# MCU.net
KiCad netlist of a schematic drawn in Altium Designer
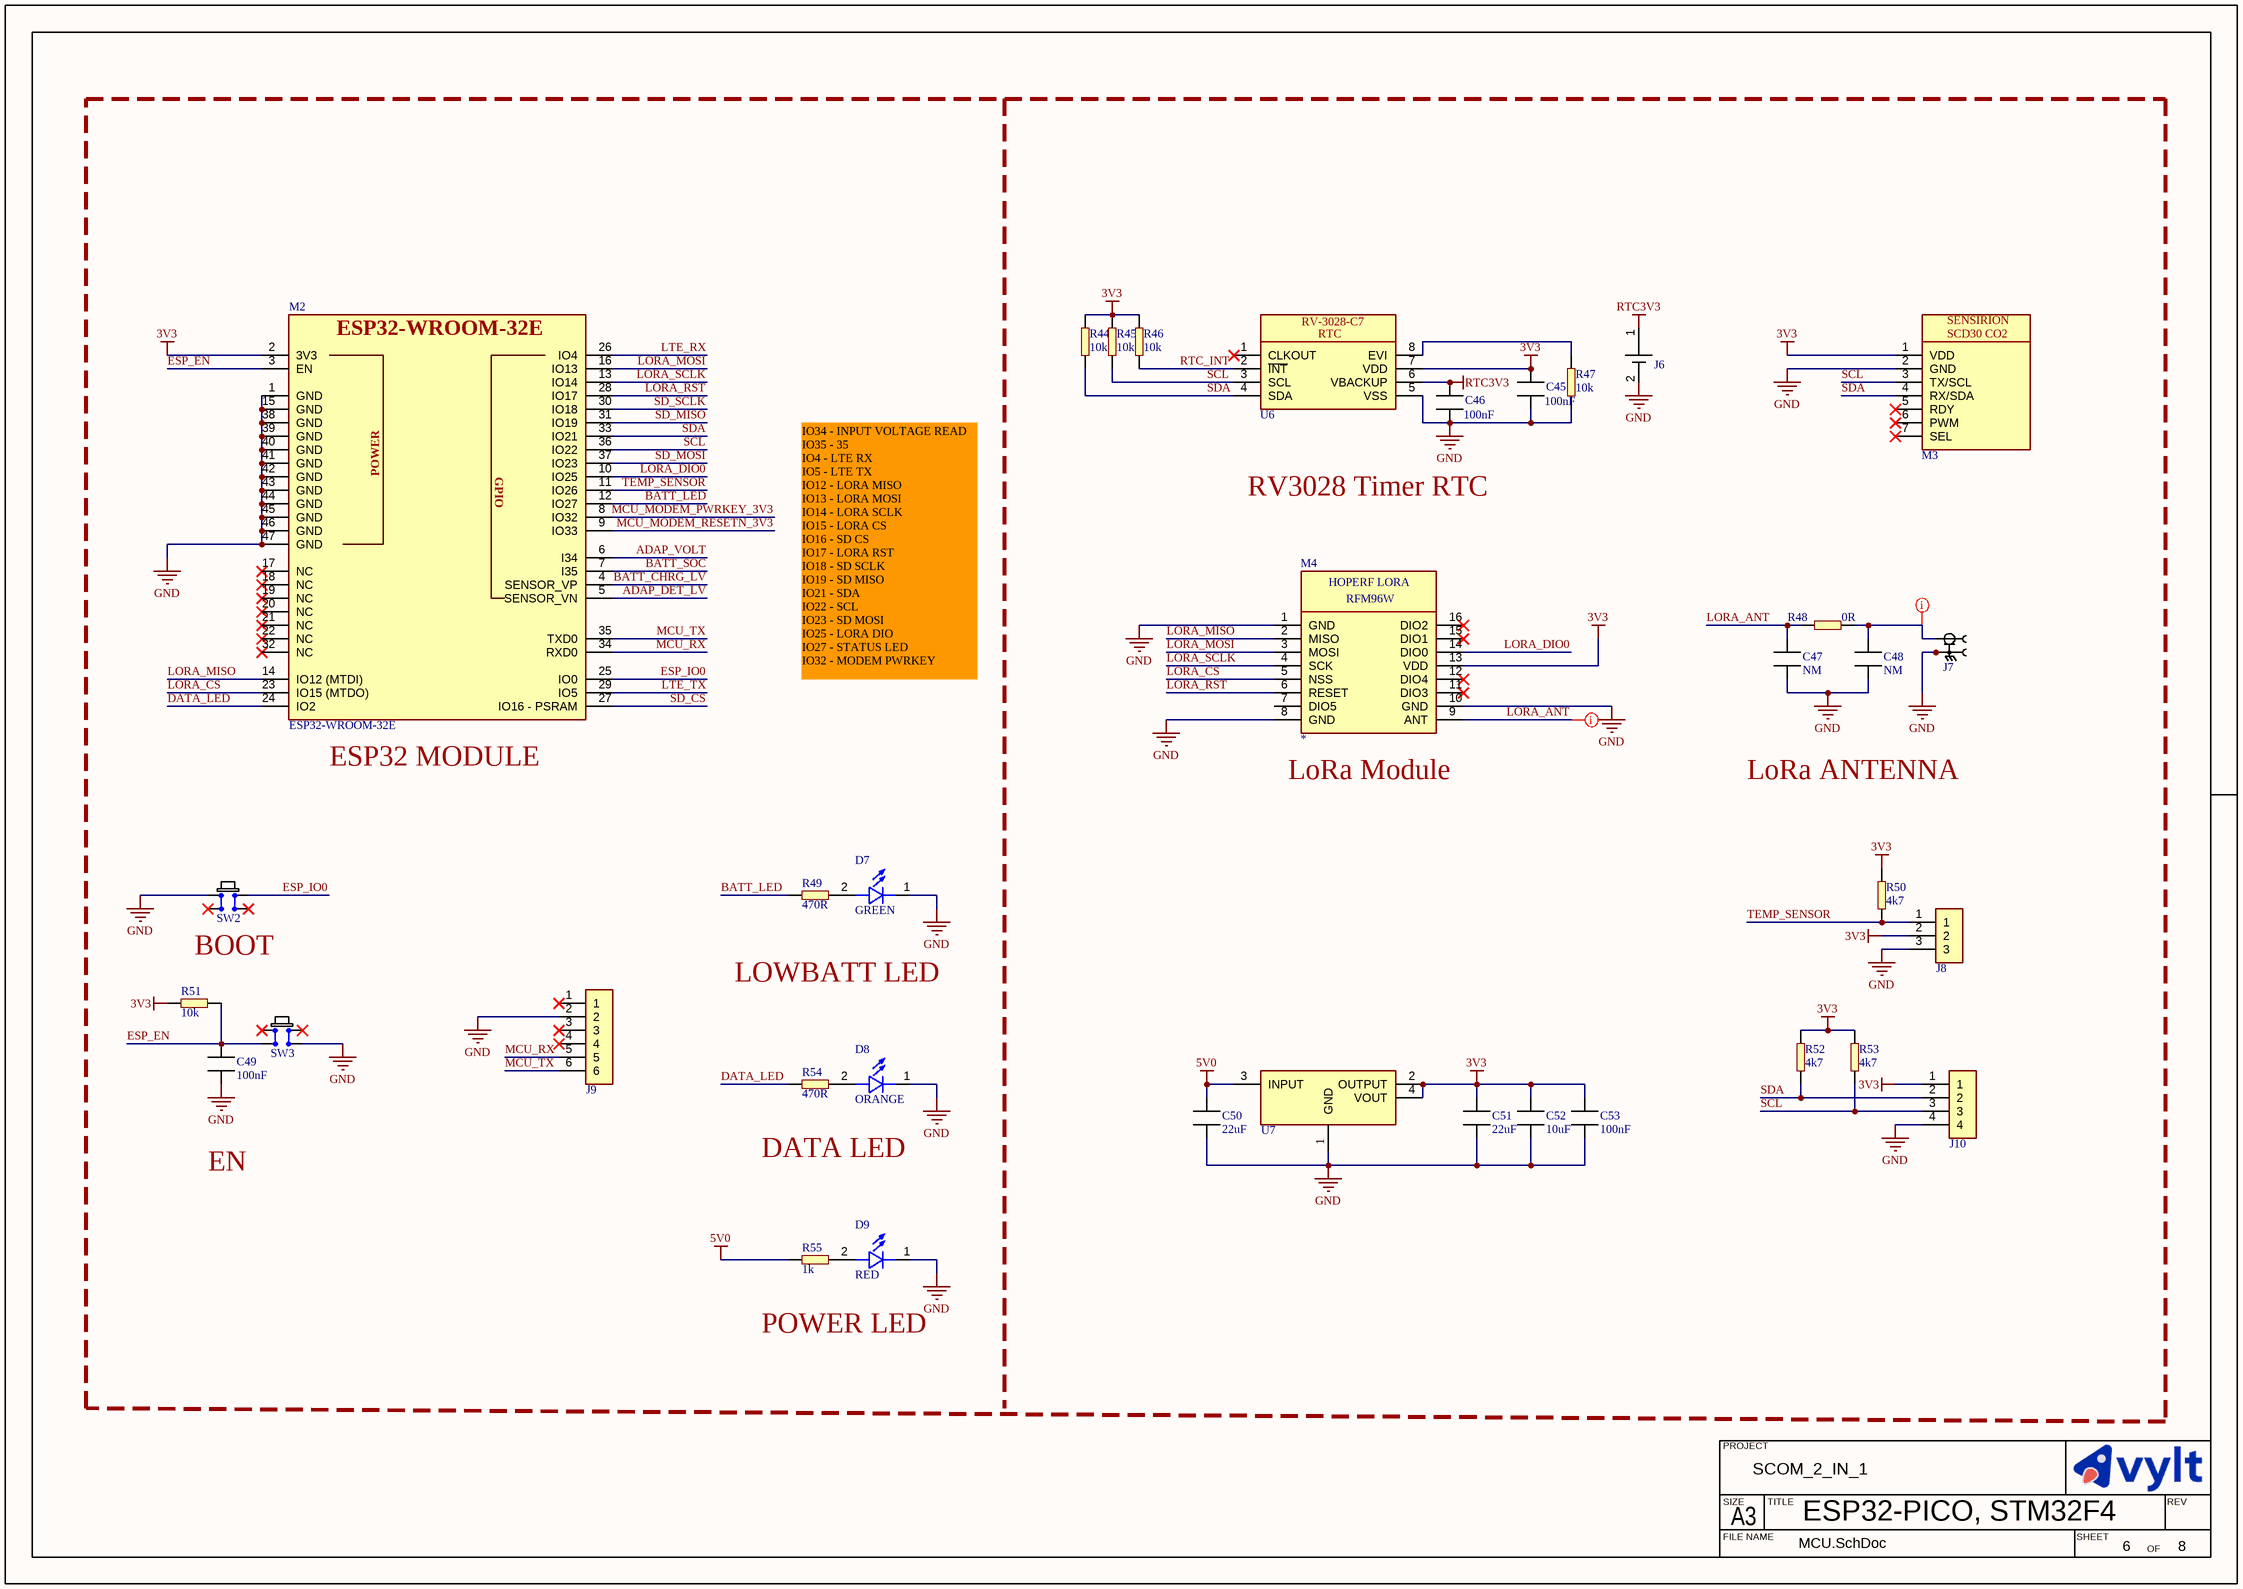
[diagram p0: MCU.SchDoc]

(export (version "E")
  (design (tool "Eeschema 10.0.6"))
  (components
    (comp (ref "C45")
      (value "100nF")
      (footprint "CAPC2012X13L")
      (description "1uF 105 0805 (2012 metric) 50V X7R MLCC SMD")
      (fields (field (name "Comment") "MLCC_0805"))
      (libsource (lib "Capacitor") (part "MLCC_0805"))
    )
    (comp (ref "C46")
      (value "100nF")
      (footprint "CAPC2012X13L")
      (description "1uF 105 0805 (2012 metric) 50V X7R MLCC SMD")
      (fields (field (name "Comment") "MLCC_0805"))
      (libsource (lib "Capacitor") (part "MLCC_0805"))
    )
    (comp (ref "C47")
      (value "NM")
      (footprint "CAPC0603X03L")
      (description "Chip Capacitor, 2-Leads, Body 0.60x0.30mm, IPC High Density")
      (fields (field (name "Comment") "ERP_102-1"))
      (libsource (lib "Capacitor") (part "MLCC_0201"))
    )
    (comp (ref "C48")
      (value "NM")
      (footprint "CAPC0603X03L")
      (description "Chip Capacitor, 2-Leads, Body 0.60x0.30mm, IPC High Density")
      (fields (field (name "Comment") "ERP_102-1"))
      (libsource (lib "Capacitor") (part "MLCC_0201"))
    )
    (comp (ref "C49")
      (value "100nF")
      (footprint "CAPC2012X13L")
      (description "Chip Capacitor, 2-Leads, Body 2.00x1.25mm, IPC High Density")
      (fields (field (name "Comment") "MLCC_0805"))
      (libsource (lib "Capacitor") (part "MLCC_0805"))
    )
    (comp (ref "C50")
      (value "22uF")
      (footprint "CAPC2012X13L")
      (description "Chip Capacitor, 2-Leads, Body 2.00x1.25mm, IPC High Density")
      (fields (field (name "Comment") "MLCC_0805"))
      (libsource (lib "Capacitor") (part "MLCC_0805"))
    )
    (comp (ref "C51")
      (value "22uF")
      (footprint "CAPC2012X13L")
      (description "Chip Capacitor, 2-Leads, Body 2.00x1.25mm, IPC High Density")
      (fields (field (name "Comment") "MLCC_0805"))
      (libsource (lib "Capacitor") (part "MLCC_0805"))
    )
    (comp (ref "C52")
      (value "10uF")
      (footprint "CAPC2012X13L")
      (description "Chip Capacitor, 2-Leads, Body 2.00x1.25mm, IPC High Density")
      (fields (field (name "Comment") "MLCC_0805"))
      (libsource (lib "Capacitor") (part "MLCC_0805"))
    )
    (comp (ref "C53")
      (value "100nF")
      (footprint "CAPC2012X13L")
      (description "Chip Capacitor, 2-Leads, Body 2.00x1.25mm, IPC High Density")
      (fields (field (name "Comment") "MLCC_0805"))
      (libsource (lib "Capacitor") (part "MLCC_0805"))
    )
    (comp (ref "D7")
      (value "GREEN")
      (footprint "LED_1206")
      (description "LED CLEAR 1206 SMD")
      (fields (field (name "Comment") "LED_1206"))
      (libsource (lib "LED") (part "LED_1206"))
    )
    (comp (ref "D8")
      (value "ORANGE")
      (footprint "LED_1206")
      (description "LED CLEAR 1206 SMD")
      (fields (field (name "Comment") "LED_1206"))
      (libsource (lib "LED") (part "LED_1206"))
    )
    (comp (ref "D9")
      (value "RED")
      (footprint "LED_1206")
      (description "LED CLEAR 1206 SMD")
      (fields (field (name "Comment") "LED_1206"))
      (libsource (lib "LED") (part "LED_1206"))
    )
    (comp (ref "J6")
      (value "CR1220-BH")
      (footprint "CR1220-BH")
      (description "BATTERY HOLDER COIN 12.5MM SMD")
      (libsource (lib "Connectors") (part "CR1220-BH"))
    )
    (comp (ref "J7")
      (value "ERP_148-1")
      (footprint "uFL_50R")
      (description "uFL_50R")
      (libsource (lib "RF_Connector") (part "uFL_50R"))
    )
    (comp (ref "J8")
      (value "Terminal_Block_3Pin_5.08P")
      (footprint "TB_PLUG_5.08P_3P")
      (description "3PINS TERMINAL BLOCK 5.08 PITCH")
      (libsource (lib "Connectors") (part "Terminal_Block_3Pin_5.08P"))
    )
    (comp (ref "J9")
      (value "ERP_148-2")
      (footprint "6PX1R_F")
      (description "6PX1R Female Header")
      (libsource (lib "PinHeader") (part "6PX1R_F"))
    )
    (comp (ref "J10")
      (value "Terminal_Block_4Pin_5.08P")
      (footprint "TB_PLUG_5.08P_4P")
      (description "4PINS TERMINAL BLOCK 5.08 PITCH")
      (libsource (lib "Connectors") (part "Terminal_Block_4Pin_5.08P"))
    )
    (comp (ref "M2")
      (value "ESP32-WROOM-32E")
      (footprint "ESP32-WROOM-32UE")
      (description "ESP32-WROOM-32E Module")
      (libsource (lib "ESP") (part "ESP32-WROOM-32E"))
    )
    (comp (ref "M3")
      (value "SCD30")
      (footprint "SCD30")
      (description "CO₂ accuracy of ±(30 ppm + 3% MV) @400-10000 ppm")
      (libsource (lib "TemperatureSensor") (part "SCD30"))
    )
    (comp (ref "M4")
      (value "RFM96W")
      (footprint "RFM96W")
      (description "LoRa 868MHz SX1276 RF Transreceiver Module RFM96W")
      (fields (field (name "ALTIUM_VALUE") "*"))
      (libsource (lib "WirelessModule") (part "RFM96W"))
    )
    (comp (ref "R44")
      (value "10k")
      (footprint "RES_0603")
      (description "RES_0603")
      (fields (field (name "Comment") "ERP_101-1"))
      (libsource (lib "") (part "RES_0603_2"))
    )
    (comp (ref "R45")
      (value "10k")
      (footprint "RES_0603")
      (description "RES_0603")
      (fields (field (name "Comment") "ERP_101-1"))
      (libsource (lib "") (part "RES_0603_2"))
    )
    (comp (ref "R46")
      (value "10k")
      (footprint "RES_0603")
      (description "RES_0603")
      (fields (field (name "Comment") "ERP_101-1"))
      (libsource (lib "") (part "RES_0603_2"))
    )
    (comp (ref "R47")
      (value "10k")
      (footprint "RES_0603")
      (description "RES_0603")
      (fields (field (name "Comment") "ERP_101-1"))
      (libsource (lib "") (part "RES_0603_2"))
    )
    (comp (ref "R48")
      (value "0R")
      (footprint "RESC0603X03L")
      (description "RES_0201")
      (fields (field (name "Comment") "ERP_101-1"))
      (libsource (lib "Resistor") (part "RES_0201"))
    )
    (comp (ref "R49")
      (value "470R")
      (footprint "RES_0603")
      (description "RES_0603")
      (fields (field (name "Comment") "ERP_101-1"))
      (libsource (lib "") (part "RES_0603_1"))
    )
    (comp (ref "R50")
      (value "4k7")
      (footprint "RES_0603")
      (description "RES_0603")
      (fields (field (name "Comment") "ERP_101-1"))
      (libsource (lib "Resistor") (part "RES_0603"))
    )
    (comp (ref "R51")
      (value "10k")
      (footprint "RES_0603")
      (description "RES_0603")
      (fields (field (name "Comment") "ERP_101-1"))
      (libsource (lib "") (part "RES_0603_1"))
    )
    (comp (ref "R52")
      (value "4k7")
      (footprint "RES_0603")
      (description "RES_0603")
      (fields (field (name "Comment") "ERP_101-1"))
      (libsource (lib "Resistor") (part "RES_0603"))
    )
    (comp (ref "R53")
      (value "4k7")
      (footprint "RES_0603")
      (description "RES_0603")
      (fields (field (name "Comment") "ERP_101-1"))
      (libsource (lib "Resistor") (part "RES_0603"))
    )
    (comp (ref "R54")
      (value "470R")
      (footprint "RES_0603")
      (description "RES_0603")
      (fields (field (name "Comment") "ERP_101-1"))
      (libsource (lib "") (part "RES_0603_1"))
    )
    (comp (ref "R55")
      (value "1k")
      (footprint "RES_0603")
      (description "RES_0603")
      (fields (field (name "Comment") "ERP_101-1"))
      (libsource (lib "") (part "RES_0603_1"))
    )
    (comp (ref "SW2")
      (value "Generic6X6")
      (footprint "Generic6X6")
      (description "Tactile Switch SPST-NO Top Actuated Surface Mount")
      (libsource (lib "Switch") (part "Generic6X6"))
    )
    (comp (ref "SW3")
      (value "Generic6X6")
      (footprint "Generic6X6")
      (description "Tactile Switch SPST-NO Top Actuated Surface Mount")
      (libsource (lib "Switch") (part "Generic6X6"))
    )
    (comp (ref "U6")
      (value "RV-3028-C7")
      (footprint "RV-3028-C7")
      (description "IC RTC CLK/CALENDAR I2C 8SON")
      (libsource (lib "RTC") (part "RV-3028-C7"))
    )
    (comp (ref "U7")
      (value "ERP_123-1")
      (footprint "AMS1117_SOT223")
      (description "AMS1117 LDO")
      (libsource (lib "VoltageRegulator") (part "AMS1117_SOT223"))
    )
  )
  (nets
    (net (code "1") (name "/ADAP_DET_LV") (class "Default")
      (node (ref "M2") (pin "5") (pinfunction "SENSOR_VN_5") (pintype "passive"))
    )
    (net (code "2") (name "/ADAP_VOLT") (class "Default")
      (node (ref "M2") (pin "6") (pinfunction "I34_6") (pintype "passive"))
    )
    (net (code "3") (name "/BATT_CHRG_LV") (class "Default")
      (node (ref "M2") (pin "4") (pinfunction "SENSOR_VP_4") (pintype "passive"))
    )
    (net (code "4") (name "/BATT_LED") (class "Default")
      (node (ref "M2") (pin "12") (pinfunction "IO27_12") (pintype "passive"))
      (node (ref "R49") (pin "2") (pinfunction "2_2") (pintype "passive"))
    )
    (net (code "5") (name "/BATT_SOC") (class "Default")
      (node (ref "M2") (pin "7") (pinfunction "I35_7") (pintype "passive"))
    )
    (net (code "6") (name "/DATA_LED") (class "Default")
      (node (ref "M2") (pin "24") (pinfunction "IO2_24") (pintype "passive"))
      (node (ref "R54") (pin "2") (pinfunction "2_2") (pintype "passive"))
    )
    (net (code "7") (name "/ESP_EN") (class "Default")
      (node (ref "C49") (pin "1") (pinfunction "1_1") (pintype "passive"))
      (node (ref "M2") (pin "3") (pinfunction "EN_3") (pintype "passive"))
      (node (ref "R51") (pin "1") (pinfunction "1_1") (pintype "passive"))
      (node (ref "SW3") (pin "2") (pinfunction "NO_2") (pintype "passive"))
    )
    (net (code "8") (name "/ESP_IO0") (class "Default")
      (node (ref "M2") (pin "25") (pinfunction "IO0_25") (pintype "passive"))
      (node (ref "SW2") (pin "3") (pinfunction "COM_3") (pintype "passive"))
    )
    (net (code "9") (name "/LORA_ANT") (class "Default")
      (node (ref "C47") (pin "2") (pinfunction "2_2") (pintype "passive"))
      (node (ref "M4") (pin "9") (pinfunction "ANT_9") (pintype "passive"))
      (node (ref "R48") (pin "2") (pinfunction "2_2") (pintype "passive"))
    )
    (net (code "10") (name "/LORA_CS") (class "Default")
      (node (ref "M2") (pin "23") (pinfunction "IO15_(MTDO)_23") (pintype "passive"))
      (node (ref "M4") (pin "5") (pinfunction "NSS_5") (pintype "passive"))
    )
    (net (code "11") (name "/LORA_DIO0") (class "Default")
      (node (ref "M2") (pin "10") (pinfunction "IO25_10") (pintype "passive"))
      (node (ref "M4") (pin "14") (pinfunction "DIO0_14") (pintype "passive"))
    )
    (net (code "12") (name "/LORA_MISO") (class "Default")
      (node (ref "M2") (pin "14") (pinfunction "IO12_(MTDI)_14") (pintype "passive"))
      (node (ref "M4") (pin "2") (pinfunction "MISO_2") (pintype "passive"))
    )
    (net (code "13") (name "/LORA_MOSI") (class "Default")
      (node (ref "M2") (pin "16") (pinfunction "IO13_16") (pintype "passive"))
      (node (ref "M4") (pin "3") (pinfunction "MOSI_3") (pintype "passive"))
    )
    (net (code "14") (name "/LORA_RST") (class "Default")
      (node (ref "M2") (pin "28") (pinfunction "IO17_28") (pintype "passive"))
      (node (ref "M4") (pin "6") (pinfunction "RESET_6") (pintype "passive"))
    )
    (net (code "15") (name "/LORA_SCLK") (class "Default")
      (node (ref "M2") (pin "13") (pinfunction "IO14_13") (pintype "passive"))
      (node (ref "M4") (pin "4") (pinfunction "SCK_4") (pintype "passive"))
    )
    (net (code "16") (name "/LTE_RX") (class "Default")
      (node (ref "M2") (pin "26") (pinfunction "IO4_26") (pintype "passive"))
    )
    (net (code "17") (name "/LTE_TX") (class "Default")
      (node (ref "M2") (pin "29") (pinfunction "IO5_29") (pintype "passive"))
    )
    (net (code "18") (name "/MCU_MODEM_PWRKEY_3V3") (class "Default")
      (node (ref "M2") (pin "8") (pinfunction "IO32_8") (pintype "passive"))
    )
    (net (code "19") (name "/MCU_MODEM_RESETN_3V3") (class "Default")
      (node (ref "M2") (pin "9") (pinfunction "IO33_9") (pintype "passive"))
    )
    (net (code "20") (name "/MCU_RX") (class "Default")
      (node (ref "J9") (pin "5") (pinfunction "5_5") (pintype "passive"))
      (node (ref "M2") (pin "34") (pinfunction "RXD0_34") (pintype "passive"))
    )
    (net (code "21") (name "/MCU_TX") (class "Default")
      (node (ref "J9") (pin "6") (pinfunction "6_6") (pintype "passive"))
      (node (ref "M2") (pin "35") (pinfunction "TXD0_35") (pintype "passive"))
    )
    (net (code "22") (name "/RTC_INT") (class "Default")
      (node (ref "R46") (pin "1") (pinfunction "1_1") (pintype "passive"))
      (node (ref "U6") (pin "2") (pinfunction "~{INT}_2") (pintype "passive"))
    )
    (net (code "23") (name "/SCL") (class "Default")
      (node (ref "J10") (pin "3") (pinfunction "3_3") (pintype "passive"))
      (node (ref "M2") (pin "36") (pinfunction "IO22_36") (pintype "passive"))
      (node (ref "M3") (pin "3") (pinfunction "TX/SCL_3") (pintype "passive"))
      (node (ref "R45") (pin "1") (pinfunction "1_1") (pintype "passive"))
      (node (ref "R53") (pin "2") (pinfunction "2_2") (pintype "passive"))
      (node (ref "U6") (pin "3") (pinfunction "SCL_3") (pintype "passive"))
    )
    (net (code "24") (name "/SDA") (class "Default")
      (node (ref "J10") (pin "2") (pinfunction "2_2") (pintype "passive"))
      (node (ref "M2") (pin "33") (pinfunction "IO21_33") (pintype "passive"))
      (node (ref "M3") (pin "4") (pinfunction "RX/SDA_4") (pintype "passive"))
      (node (ref "R44") (pin "1") (pinfunction "1_1") (pintype "passive"))
      (node (ref "R52") (pin "2") (pinfunction "2_2") (pintype "passive"))
      (node (ref "U6") (pin "4") (pinfunction "SDA_4") (pintype "passive"))
    )
    (net (code "25") (name "/SD_CS") (class "Default")
      (node (ref "M2") (pin "27") (pinfunction "IO16_-_PSRAM_27") (pintype "passive"))
    )
    (net (code "26") (name "/SD_MISO") (class "Default")
      (node (ref "M2") (pin "31") (pinfunction "IO19_31") (pintype "passive"))
    )
    (net (code "27") (name "/SD_MOSI") (class "Default")
      (node (ref "M2") (pin "37") (pinfunction "IO23_37") (pintype "passive"))
    )
    (net (code "28") (name "/SD_SCLK") (class "Default")
      (node (ref "M2") (pin "30") (pinfunction "IO18_30") (pintype "passive"))
    )
    (net (code "29") (name "/TEMP_SENSOR") (class "Default")
      (node (ref "J8") (pin "1") (pinfunction "1_1") (pintype "passive"))
      (node (ref "M2") (pin "11") (pinfunction "IO26_11") (pintype "passive"))
      (node (ref "R50") (pin "2") (pinfunction "2_2") (pintype "passive"))
    )
    (net (code "30") (name "3V3") (class "Default")
      (node (ref "C45") (pin "1") (pinfunction "1_1") (pintype "passive"))
      (node (ref "C51") (pin "1") (pinfunction "1_1") (pintype "passive"))
      (node (ref "C52") (pin "1") (pinfunction "1_1") (pintype "passive"))
      (node (ref "C53") (pin "1") (pinfunction "1_1") (pintype "passive"))
      (node (ref "J10") (pin "1") (pinfunction "1_1") (pintype "passive"))
      (node (ref "J8") (pin "2") (pinfunction "2_2") (pintype "passive"))
      (node (ref "M2") (pin "2") (pinfunction "3V3_2") (pintype "passive"))
      (node (ref "M3") (pin "1") (pinfunction "VDD_1") (pintype "passive"))
      (node (ref "M4") (pin "13") (pinfunction "VDD_13") (pintype "passive"))
      (node (ref "R44") (pin "2") (pinfunction "2_2") (pintype "passive"))
      (node (ref "R45") (pin "2") (pinfunction "2_2") (pintype "passive"))
      (node (ref "R46") (pin "2") (pinfunction "2_2") (pintype "passive"))
      (node (ref "R50") (pin "1") (pinfunction "1_1") (pintype "passive"))
      (node (ref "R51") (pin "2") (pinfunction "2_2") (pintype "passive"))
      (node (ref "R52") (pin "1") (pinfunction "1_1") (pintype "passive"))
      (node (ref "R53") (pin "1") (pinfunction "1_1") (pintype "passive"))
      (node (ref "U6") (pin "7") (pinfunction "VDD_7") (pintype "passive"))
      (node (ref "U7") (pin "2") (pinfunction "OUTPUT_2") (pintype "passive"))
      (node (ref "U7") (pin "4") (pinfunction "VOUT_4") (pintype "passive"))
    )
    (net (code "31") (name "5V0") (class "Default")
      (node (ref "C50") (pin "1") (pinfunction "1_1") (pintype "passive"))
      (node (ref "R55") (pin "2") (pinfunction "2_2") (pintype "passive"))
      (node (ref "U7") (pin "3") (pinfunction "INPUT_3") (pintype "passive"))
    )
    (net (code "32") (name "GND") (class "Default")
      (node (ref "C45") (pin "2") (pinfunction "2_2") (pintype "passive"))
      (node (ref "C46") (pin "2") (pinfunction "2_2") (pintype "passive"))
      (node (ref "C47") (pin "1") (pinfunction "1_1") (pintype "passive"))
      (node (ref "C48") (pin "1") (pinfunction "1_1") (pintype "passive"))
      (node (ref "C49") (pin "2") (pinfunction "2_2") (pintype "passive"))
      (node (ref "C50") (pin "2") (pinfunction "2_2") (pintype "passive"))
      (node (ref "C51") (pin "2") (pinfunction "2_2") (pintype "passive"))
      (node (ref "C52") (pin "2") (pinfunction "2_2") (pintype "passive"))
      (node (ref "C53") (pin "2") (pinfunction "2_2") (pintype "passive"))
      (node (ref "D7") (pin "1") (pinfunction "1_1") (pintype "passive"))
      (node (ref "D8") (pin "1") (pinfunction "1_1") (pintype "passive"))
      (node (ref "D9") (pin "1") (pinfunction "1_1") (pintype "passive"))
      (node (ref "J10") (pin "4") (pinfunction "4_4") (pintype "passive"))
      (node (ref "J6") (pin "2") (pinfunction "-_2") (pintype "passive"))
      (node (ref "J7") (pin "1") (pinfunction "1_1") (pintype "passive"))
      (node (ref "J7") (pin "2") (pinfunction "2_2") (pintype "passive"))
      (node (ref "J8") (pin "3") (pinfunction "3_3") (pintype "passive"))
      (node (ref "J9") (pin "2") (pinfunction "2_2") (pintype "passive"))
      (node (ref "M2") (pin "1") (pinfunction "GND_1") (pintype "passive"))
      (node (ref "M2") (pin "15") (pinfunction "GND_15") (pintype "passive"))
      (node (ref "M2") (pin "38") (pinfunction "GND_38") (pintype "passive"))
      (node (ref "M2") (pin "39") (pinfunction "GND_39") (pintype "passive"))
      (node (ref "M2") (pin "40") (pinfunction "GND_40") (pintype "passive"))
      (node (ref "M2") (pin "41") (pinfunction "GND_41") (pintype "passive"))
      (node (ref "M2") (pin "42") (pinfunction "GND_42") (pintype "passive"))
      (node (ref "M2") (pin "43") (pinfunction "GND_43") (pintype "passive"))
      (node (ref "M2") (pin "44") (pinfunction "GND_44") (pintype "passive"))
      (node (ref "M2") (pin "45") (pinfunction "GND_45") (pintype "passive"))
      (node (ref "M2") (pin "46") (pinfunction "GND_46") (pintype "passive"))
      (node (ref "M2") (pin "47") (pinfunction "GND_47") (pintype "passive"))
      (node (ref "M3") (pin "2") (pinfunction "GND_2") (pintype "passive"))
      (node (ref "M4") (pin "1") (pinfunction "GND_1") (pintype "passive"))
      (node (ref "M4") (pin "10") (pinfunction "GND_10") (pintype "passive"))
      (node (ref "M4") (pin "8") (pinfunction "GND_8") (pintype "passive"))
      (node (ref "R47") (pin "1") (pinfunction "1_1") (pintype "passive"))
      (node (ref "SW2") (pin "1") (pinfunction "NO_1") (pintype "passive"))
      (node (ref "SW3") (pin "4") (pinfunction "COM_4") (pintype "passive"))
      (node (ref "U6") (pin "5") (pinfunction "VSS_5") (pintype "passive"))
      (node (ref "U7") (pin "1") (pinfunction "GND_1") (pintype "power_in"))
    )
    (net (code "33") (name "Net-(C48-Pad2)") (class "Default")
      (node (ref "C48") (pin "2") (pinfunction "2_2") (pintype "passive"))
      (node (ref "J7") (pin "3") (pinfunction "3_3") (pintype "passive"))
      (node (ref "R48") (pin "1") (pinfunction "1_1") (pintype "passive"))
    )
    (net (code "34") (name "Net-(D7-Pad2)") (class "Default")
      (node (ref "D7") (pin "2") (pinfunction "2_2") (pintype "passive"))
      (node (ref "R49") (pin "1") (pinfunction "1_1") (pintype "passive"))
    )
    (net (code "35") (name "Net-(D8-Pad2)") (class "Default")
      (node (ref "D8") (pin "2") (pinfunction "2_2") (pintype "passive"))
      (node (ref "R54") (pin "1") (pinfunction "1_1") (pintype "passive"))
    )
    (net (code "36") (name "Net-(D9-Pad2)") (class "Default")
      (node (ref "D9") (pin "2") (pinfunction "2_2") (pintype "passive"))
      (node (ref "R55") (pin "1") (pinfunction "1_1") (pintype "passive"))
    )
    (net (code "37") (name "Net-(U6-EVI)") (class "Default")
      (node (ref "R47") (pin "2") (pinfunction "2_2") (pintype "passive"))
      (node (ref "U6") (pin "8") (pinfunction "EVI_8") (pintype "passive"))
    )
    (net (code "38") (name "RTC3V3") (class "Default")
      (node (ref "C46") (pin "1") (pinfunction "1_1") (pintype "passive"))
      (node (ref "J6") (pin "1") (pinfunction "+_1") (pintype "passive"))
      (node (ref "U6") (pin "6") (pinfunction "VBACKUP_6") (pintype "passive"))
    )
    (net (code "39") (name "unconnected-(J9-Pad1)") (class "Default")
      (node (ref "J9") (pin "1") (pinfunction "1_1") (pintype "passive+no_connect"))
    )
    (net (code "40") (name "unconnected-(J9-Pad3)") (class "Default")
      (node (ref "J9") (pin "3") (pinfunction "3_3") (pintype "passive+no_connect"))
    )
    (net (code "41") (name "unconnected-(J9-Pad4)") (class "Default")
      (node (ref "J9") (pin "4") (pinfunction "4_4") (pintype "passive+no_connect"))
    )
    (net (code "42") (name "unconnected-(M2-NC-Pad17)") (class "Default")
      (node (ref "M2") (pin "17") (pinfunction "NC_17") (pintype "passive+no_connect"))
    )
    (net (code "43") (name "unconnected-(M2-NC-Pad18)") (class "Default")
      (node (ref "M2") (pin "18") (pinfunction "NC_18") (pintype "passive+no_connect"))
    )
    (net (code "44") (name "unconnected-(M2-NC-Pad19)") (class "Default")
      (node (ref "M2") (pin "19") (pinfunction "NC_19") (pintype "passive+no_connect"))
    )
    (net (code "45") (name "unconnected-(M2-NC-Pad20)") (class "Default")
      (node (ref "M2") (pin "20") (pinfunction "NC_20") (pintype "passive+no_connect"))
    )
    (net (code "46") (name "unconnected-(M2-NC-Pad21)") (class "Default")
      (node (ref "M2") (pin "21") (pinfunction "NC_21") (pintype "passive+no_connect"))
    )
    (net (code "47") (name "unconnected-(M2-NC-Pad22)") (class "Default")
      (node (ref "M2") (pin "22") (pinfunction "NC_22") (pintype "passive+no_connect"))
    )
    (net (code "48") (name "unconnected-(M2-NC-Pad32)") (class "Default")
      (node (ref "M2") (pin "32") (pinfunction "NC_32") (pintype "passive+no_connect"))
    )
    (net (code "49") (name "unconnected-(M3-PWM-Pad6)") (class "Default")
      (node (ref "M3") (pin "6") (pinfunction "PWM_6") (pintype "passive+no_connect"))
    )
    (net (code "50") (name "unconnected-(M3-RDY-Pad5)") (class "Default")
      (node (ref "M3") (pin "5") (pinfunction "RDY_5") (pintype "passive+no_connect"))
    )
    (net (code "51") (name "unconnected-(M3-SEL-Pad7)") (class "Default")
      (node (ref "M3") (pin "7") (pinfunction "SEL_7") (pintype "passive+no_connect"))
    )
    (net (code "52") (name "unconnected-(M4-DIO1-Pad15)") (class "Default")
      (node (ref "M4") (pin "15") (pinfunction "DIO1_15") (pintype "passive+no_connect"))
    )
    (net (code "53") (name "unconnected-(M4-DIO2-Pad16)") (class "Default")
      (node (ref "M4") (pin "16") (pinfunction "DIO2_16") (pintype "passive+no_connect"))
    )
    (net (code "54") (name "unconnected-(M4-DIO3-Pad11)") (class "Default")
      (node (ref "M4") (pin "11") (pinfunction "DIO3_11") (pintype "passive+no_connect"))
    )
    (net (code "55") (name "unconnected-(M4-DIO4-Pad12)") (class "Default")
      (node (ref "M4") (pin "12") (pinfunction "DIO4_12") (pintype "passive+no_connect"))
    )
    (net (code "56") (name "unconnected-(M4-DIO5-Pad7)") (class "Default")
      (node (ref "M4") (pin "7") (pinfunction "DIO5_7") (pintype "passive"))
    )
    (net (code "57") (name "unconnected-(SW2-COM-Pad4)") (class "Default")
      (node (ref "SW2") (pin "4") (pinfunction "COM_4") (pintype "passive+no_connect"))
    )
    (net (code "58") (name "unconnected-(SW2-NO-Pad2)") (class "Default")
      (node (ref "SW2") (pin "2") (pinfunction "NO_2") (pintype "passive+no_connect"))
    )
    (net (code "59") (name "unconnected-(SW3-COM-Pad3)") (class "Default")
      (node (ref "SW3") (pin "3") (pinfunction "COM_3") (pintype "passive+no_connect"))
    )
    (net (code "60") (name "unconnected-(SW3-NO-Pad1)") (class "Default")
      (node (ref "SW3") (pin "1") (pinfunction "NO_1") (pintype "passive+no_connect"))
    )
    (net (code "61") (name "unconnected-(U6-CLKOUT-Pad1)") (class "Default")
      (node (ref "U6") (pin "1") (pinfunction "CLKOUT_1") (pintype "passive+no_connect"))
    )
  )
)
